# Microcontroller.net
KiCad netlist of a schematic drawn in Altium Designer
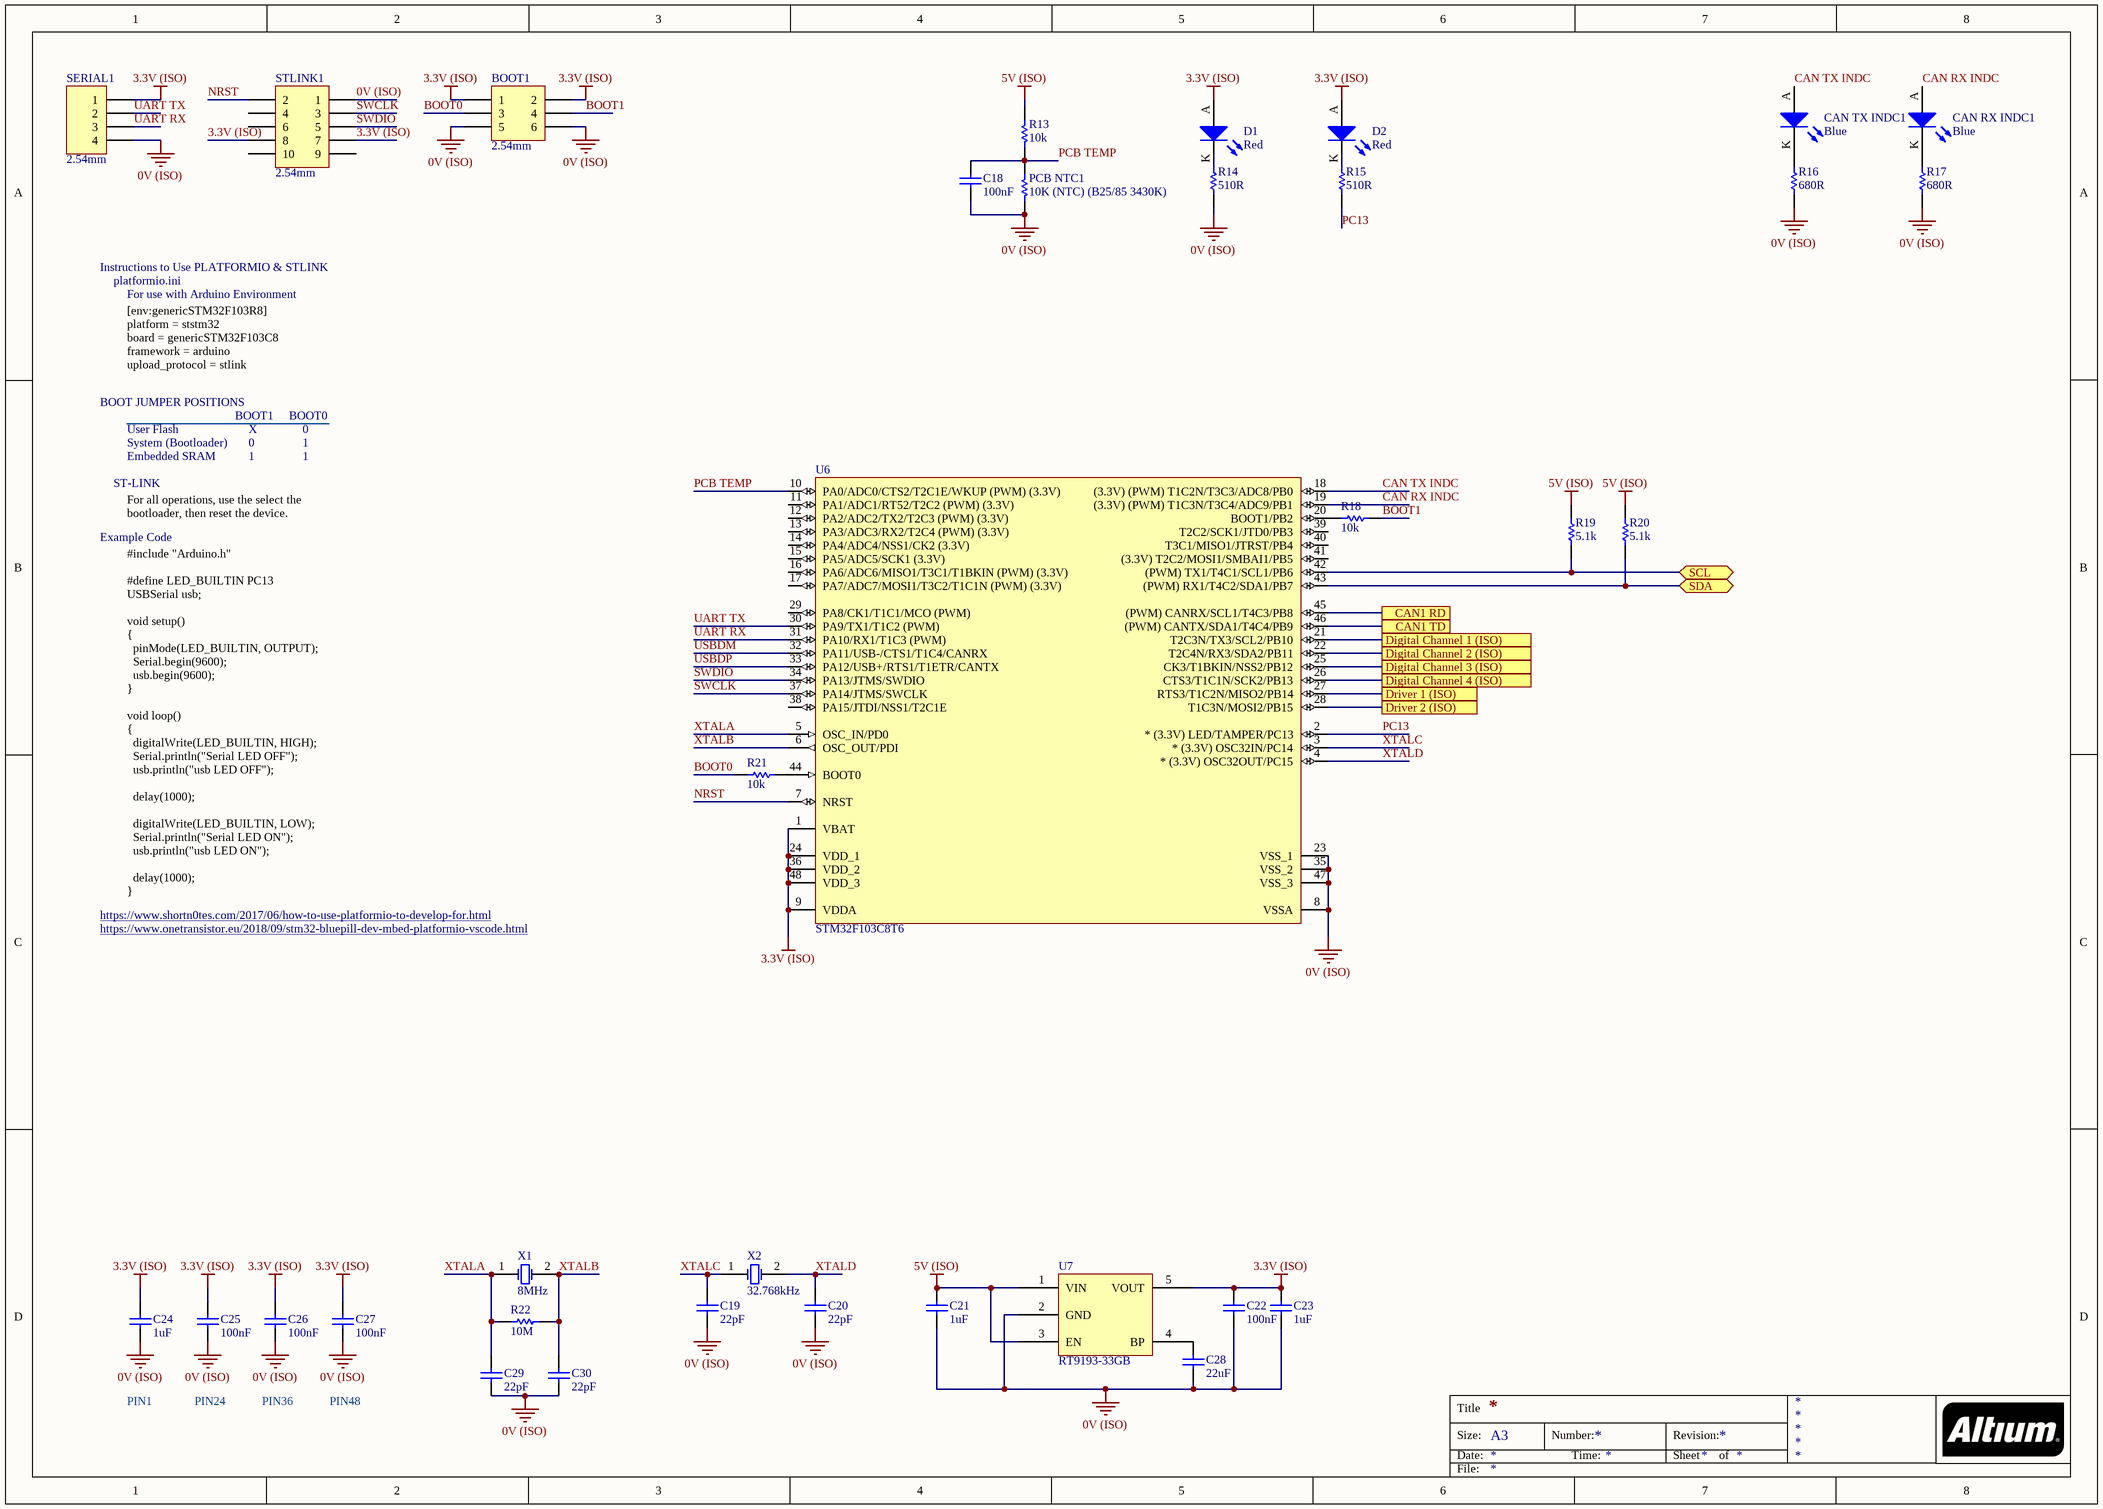
[diagram p0: Microcontroller.SchDoc]

(export (version "E")
  (design (tool "Eeschema 10.0.6"))
  (components
    (comp (ref "BOOT1")
      (value "2.54mm")
      (footprint "TH 2.54mm Header 2x3")
      (fields (field (name "PART NUMBER") "TH 2.54mm Header 2x3") (field (name "CONTACT") "NA"))
      (libsource (lib "ts_20-standard-connectors") (part "Header 2x3"))
    )
    (comp (ref "C18")
      (value "100nF")
      (footprint "0805")
      (fields
        (field (name "PART NUMBER") "GCM21BR71E104KA37L")
        (field (name "TOLERANCE") "10%")
        (field (name "MANUFACTURER") "muRata")
      )
      (libsource (lib "ts_20-standard-library") (part "Capacitor"))
    )
    (comp (ref "C19")
      (value "22pF")
      (footprint "0805")
      (fields
        (field (name "PART NUMBER") "GCM21B5C1H220JA37L")
        (field (name "TOLERANCE") "5%")
        (field (name "MANUFACTURER") "muRata")
      )
      (libsource (lib "ts_20-standard-library") (part "Capacitor"))
    )
    (comp (ref "C20")
      (value "22pF")
      (footprint "0805")
      (fields
        (field (name "PART NUMBER") "GCM21B5C1H220JA37L")
        (field (name "TOLERANCE") "5%")
        (field (name "MANUFACTURER") "muRata")
      )
      (libsource (lib "ts_20-standard-library") (part "Capacitor"))
    )
    (comp (ref "C21")
      (value "1uF")
      (footprint "0805")
      (fields
        (field (name "PART NUMBER") "AC0805KKX7R8BB105")
        (field (name "TOLERANCE") "10%")
        (field (name "MANUFACTURER") "YAGEO")
      )
      (libsource (lib "ts_20-standard-library") (part "Capacitor"))
    )
    (comp (ref "C22")
      (value "100nF")
      (footprint "0805")
      (fields
        (field (name "PART NUMBER") "GCM21BR71E104KA37L")
        (field (name "TOLERANCE") "10%")
        (field (name "MANUFACTURER") "muRata")
      )
      (libsource (lib "ts_20-standard-library") (part "Capacitor"))
    )
    (comp (ref "C23")
      (value "1uF")
      (footprint "0805")
      (fields
        (field (name "PART NUMBER") "AC0805KKX7R8BB105")
        (field (name "TOLERANCE") "10%")
        (field (name "MANUFACTURER") "YAGEO")
      )
      (libsource (lib "ts_20-standard-library") (part "Capacitor"))
    )
    (comp (ref "C24")
      (value "1uF")
      (footprint "0805")
      (fields
        (field (name "PART NUMBER") "AC0805KKX7R8BB105")
        (field (name "TOLERANCE") "10%")
        (field (name "MANUFACTURER") "YAGEO")
      )
      (libsource (lib "ts_20-standard-library") (part "Capacitor"))
    )
    (comp (ref "C25")
      (value "100nF")
      (footprint "0805")
      (fields
        (field (name "PART NUMBER") "GCM21BR71E104KA37L")
        (field (name "TOLERANCE") "10%")
        (field (name "MANUFACTURER") "muRata")
      )
      (libsource (lib "ts_20-standard-library") (part "Capacitor"))
    )
    (comp (ref "C26")
      (value "100nF")
      (footprint "0805")
      (fields
        (field (name "PART NUMBER") "GCM21BR71E104KA37L")
        (field (name "TOLERANCE") "10%")
        (field (name "MANUFACTURER") "muRata")
      )
      (libsource (lib "ts_20-standard-library") (part "Capacitor"))
    )
    (comp (ref "C27")
      (value "100nF")
      (footprint "0805")
      (fields
        (field (name "PART NUMBER") "GCM21BR71E104KA37L")
        (field (name "TOLERANCE") "10%")
        (field (name "MANUFACTURER") "muRata")
      )
      (libsource (lib "ts_20-standard-library") (part "Capacitor"))
    )
    (comp (ref "C28")
      (value "22uF")
      (footprint "0805")
      (fields
        (field (name "PART NUMBER") "GRM21BR61A226ME51L")
        (field (name "TOLERANCE") "20%")
        (field (name "MANUFACTURER") "muRata")
      )
      (libsource (lib "ts_20-standard-library") (part "Capacitor"))
    )
    (comp (ref "C29")
      (value "22pF")
      (footprint "0805")
      (fields
        (field (name "PART NUMBER") "GCM21B5C1H220JA37L")
        (field (name "TOLERANCE") "5%")
        (field (name "MANUFACTURER") "muRata")
      )
      (libsource (lib "ts_20-standard-library") (part "Capacitor"))
    )
    (comp (ref "C30")
      (value "22pF")
      (footprint "0805")
      (fields
        (field (name "PART NUMBER") "GCM21B5C1H220JA37L")
        (field (name "TOLERANCE") "5%")
        (field (name "MANUFACTURER") "muRata")
      )
      (libsource (lib "ts_20-standard-library") (part "Capacitor"))
    )
    (comp (ref "CAN RX INDC1")
      (value "Blue")
      (footprint "0805 LED")
      (description "LED BLUE CLEAR 2012 SMD")
      (fields
        (field (name "PART NUMBER") "SML-MN2BCTT86C")
        (field (name "MANUFACTURER") "ROHM Semiconductor")
      )
      (libsource (lib "ts_20-standard-library") (part "LED"))
    )
    (comp (ref "CAN TX INDC1")
      (value "Blue")
      (footprint "0805 LED")
      (description "LED BLUE CLEAR 2012 SMD")
      (fields
        (field (name "PART NUMBER") "SML-MN2BCTT86C")
        (field (name "MANUFACTURER") "ROHM Semiconductor")
      )
      (libsource (lib "ts_20-standard-library") (part "LED"))
    )
    (comp (ref "D1")
      (value "Red")
      (footprint "0805 LED")
      (description "Red LED Indication - Discrete 1.75V 0805 (2012 Metric)")
      (fields (field (name "MANUFACTURER") "ROHM Semiconductor") (field (name "PART NUMBER") "SML-210LTT86"))
      (libsource (lib "ts_20-standard-library") (part "LED"))
    )
    (comp (ref "D2")
      (value "Red")
      (footprint "0805 LED")
      (description "Red LED Indication - Discrete 1.75V 0805 (2012 Metric)")
      (fields (field (name "MANUFACTURER") "ROHM Semiconductor") (field (name "PART NUMBER") "SML-210LTT86"))
      (libsource (lib "ts_20-standard-library") (part "LED"))
    )
    (comp (ref "PCB NTC1")
      (value "10K (NTC) (B25/85 3430K)")
      (footprint "0805")
      (fields
        (field (name "PART NUMBER") "NTCS0805E3103FLT")
        (field (name "MANUFACTURER") "Vishay Beyschlag")
        (field (name "TOLERANCE") "0.01")
      )
      (libsource (lib "ts_20-standard-library") (part "Resistor"))
    )
    (comp (ref "R13")
      (value "10k")
      (footprint "0805")
      (fields
        (field (name "PART NUMBER") "RC0805FR0710KL")
        (field (name "MANUFACTURER") "YAGEO")
        (field (name "TOLERANCE") "0.01")
      )
      (libsource (lib "ts_20-standard-library") (part "Resistor"))
    )
    (comp (ref "R14")
      (value "510R")
      (footprint "0805")
      (fields
        (field (name "MANUFACTURER") "YAGEO")
        (field (name "PART NUMBER") "RC0805FR07510RL")
        (field (name "TOLERANCE") "0.01")
      )
      (libsource (lib "ts_20-standard-library") (part "Resistor"))
    )
    (comp (ref "R15")
      (value "510R")
      (footprint "0805")
      (fields
        (field (name "MANUFACTURER") "YAGEO")
        (field (name "PART NUMBER") "RC0805FR07510RL")
        (field (name "TOLERANCE") "0.01")
      )
      (libsource (lib "ts_20-standard-library") (part "Resistor"))
    )
    (comp (ref "R16")
      (value "680R")
      (footprint "0805")
      (fields
        (field (name "PART NUMBER") "RC0805FR07680RL")
        (field (name "MANUFACTURER") "YAGEO")
        (field (name "TOLERANCE") "0.01")
      )
      (libsource (lib "ts_20-standard-library") (part "Resistor"))
    )
    (comp (ref "R17")
      (value "680R")
      (footprint "0805")
      (fields
        (field (name "PART NUMBER") "RC0805FR07680RL")
        (field (name "MANUFACTURER") "YAGEO")
        (field (name "TOLERANCE") "0.01")
      )
      (libsource (lib "ts_20-standard-library") (part "Resistor"))
    )
    (comp (ref "R18")
      (value "10k")
      (footprint "0805")
      (fields
        (field (name "PART NUMBER") "RC0805FR0710KL")
        (field (name "MANUFACTURER") "YAGEO")
        (field (name "TOLERANCE") "0.01")
      )
      (libsource (lib "ts_20-standard-library") (part "Resistor"))
    )
    (comp (ref "R19")
      (value "5.1k")
      (footprint "0805")
      (fields
        (field (name "PART NUMBER") "RC0805FR075K1L")
        (field (name "MANUFACTURER") "YAGEO")
        (field (name "TOLERANCE") "0.01")
      )
      (libsource (lib "ts_20-standard-library") (part "Resistor"))
    )
    (comp (ref "R20")
      (value "5.1k")
      (footprint "0805")
      (fields
        (field (name "PART NUMBER") "RC0805FR075K1L")
        (field (name "MANUFACTURER") "YAGEO")
        (field (name "TOLERANCE") "0.01")
      )
      (libsource (lib "ts_20-standard-library") (part "Resistor"))
    )
    (comp (ref "R21")
      (value "10k")
      (footprint "0805")
      (fields
        (field (name "PART NUMBER") "RC0805FR0710KL")
        (field (name "MANUFACTURER") "YAGEO")
        (field (name "TOLERANCE") "0.01")
      )
      (libsource (lib "ts_20-standard-library") (part "Resistor"))
    )
    (comp (ref "R22")
      (value "10M")
      (footprint "0805")
      (fields
        (field (name "PART NUMBER") "RC0805FR0710ML")
        (field (name "MANUFACTURER") "YAGEO")
        (field (name "TOLERANCE") "0.01")
      )
      (libsource (lib "ts_20-standard-library") (part "Resistor"))
    )
    (comp (ref "SERIAL1")
      (value "2.54mm")
      (footprint "TH 2.54mm Header 1x4")
      (fields (field (name "PART NUMBER") "TH 2.54mm Header 1x4") (field (name "CONTACT") "NA"))
      (libsource (lib "ts_20-standard-connectors") (part "Header 1x4"))
    )
    (comp (ref "STLINK1")
      (value "2.54mm")
      (footprint "TH 2.54mm Header 2x5")
      (fields (field (name "PART NUMBER") "TH 2.54mm Header 2x5") (field (name "CONTACT") "NA"))
      (libsource (lib "ts_20-standard-connectors") (part "Header 2x5"))
    )
    (comp (ref "U6")
      (value "STM32F103C8T6")
      (footprint "STM 48-LQFP")
      (description "ARM® Cortex®-M3 STM32F1 Microcontroller IC 32-Bit 72MHz 64KB (64K x 8) FLASH")
      (fields
        (field (name "MANUFACTURER") "STMicroelectronics")
        (field (name "DIGIKEY PART NUMBER") "497-6063-ND")
      )
      (libsource (lib "ts_20-standard-library") (part "STM32F103C8T6"))
    )
    (comp (ref "U7")
      (value "RT9193-33GB")
      (footprint "RICHTEK SOT-23-5")
      (description "IC REG LINEAR 3.3V 300MA SOT23-5")
      (fields (field (name "MANUFACTURER") "Richtek") (field (name "DIGIKEY PART NUMBER") "1028-1014-1-ND"))
      (libsource (lib "ts_20-standard-library") (part "RT9193-33GB"))
    )
    (comp (ref "X1")
      (value "8MHz")
      (footprint "Abracon HC-49/US")
      (fields
        (field (name "PART NUMBER") "ABLS-8.000MHZ-B4-T")
        (field (name "MANUFACTURER") "Abracon LLC")
        (field (name "DIGIKEY PART NUMBER") "535-10212-2-ND")
      )
      (libsource (lib "ts_20-standard-library") (part "Crystal"))
    )
    (comp (ref "X2")
      (value "32.768kHz")
      (footprint "EPSON 2-SMD")
      (fields
        (field (name "PART NUMBER") "FC-135 32.7680KA-A5")
        (field (name "MANUFACTURER") "EPSON")
        (field (name "DIGIKEY PART NUMBER") "SER4103TR-ND")
      )
      (libsource (lib "ts_20-standard-library") (part "Crystal"))
    )
  )
  (nets
    (net (code "1") (name "/BOOT0") (class "Default")
      (node (ref "BOOT1") (pin "3") (pinfunction "3_3") (pintype "passive"))
      (node (ref "R21") (pin "1") (pinfunction "1_1") (pintype "passive"))
    )
    (net (code "2") (name "/BOOT1") (class "Default")
      (node (ref "BOOT1") (pin "4") (pinfunction "4_4") (pintype "passive"))
      (node (ref "R18") (pin "2") (pinfunction "2_2") (pintype "passive"))
    )
    (net (code "3") (name "/CAN RX INDC") (class "Default")
      (node (ref "CAN RX INDC1") (pin "A") (pinfunction "A_A") (pintype "passive"))
      (node (ref "U6") (pin "19") (pinfunction "(3.3V)_(PWM)_T1C3N/T3C4/ADC9/PB1_19") (pintype "bidirectional"))
    )
    (net (code "4") (name "/CAN TX INDC") (class "Default")
      (node (ref "CAN TX INDC1") (pin "A") (pinfunction "A_A") (pintype "passive"))
      (node (ref "U6") (pin "18") (pinfunction "(3.3V)_(PWM)_T1C2N/T3C3/ADC8/PB0_18") (pintype "bidirectional"))
    )
    (net (code "5") (name "/CAN1 RD") (class "Default")
      (node (ref "U6") (pin "45") (pinfunction "(PWM)_CANRX/SCL1/T4C3/PB8_45") (pintype "bidirectional"))
    )
    (net (code "6") (name "/CAN1 TD") (class "Default")
      (node (ref "U6") (pin "46") (pinfunction "(PWM)_CANTX/SDA1/T4C4/PB9_46") (pintype "bidirectional"))
    )
    (net (code "7") (name "/Digital Channel 1 (ISO)") (class "Default")
      (node (ref "U6") (pin "21") (pinfunction "T2C3N/TX3/SCL2/PB10_21") (pintype "bidirectional"))
    )
    (net (code "8") (name "/Digital Channel 2 (ISO)") (class "Default")
      (node (ref "U6") (pin "22") (pinfunction "T2C4N/RX3/SDA2/PB11_22") (pintype "bidirectional"))
    )
    (net (code "9") (name "/Digital Channel 3 (ISO)") (class "Default")
      (node (ref "U6") (pin "25") (pinfunction "CK3/T1BKIN/NSS2/PB12_25") (pintype "bidirectional"))
    )
    (net (code "10") (name "/Digital Channel 4 (ISO)") (class "Default")
      (node (ref "U6") (pin "26") (pinfunction "CTS3/T1C1N/SCK2/PB13_26") (pintype "bidirectional"))
    )
    (net (code "11") (name "/Driver 1 (ISO)") (class "Default")
      (node (ref "U6") (pin "27") (pinfunction "RTS3/T1C2N/MISO2/PB14_27") (pintype "bidirectional"))
    )
    (net (code "12") (name "/Driver 2 (ISO)") (class "Default")
      (node (ref "U6") (pin "28") (pinfunction "T1C3N/MOSI2/PB15_28") (pintype "bidirectional"))
    )
    (net (code "13") (name "/NRST") (class "Default")
      (node (ref "STLINK1") (pin "2") (pinfunction "2_2") (pintype "passive"))
      (node (ref "U6") (pin "7") (pinfunction "NRST_7") (pintype "bidirectional"))
    )
    (net (code "14") (name "/PC13") (class "Default")
      (node (ref "R15") (pin "1") (pinfunction "1_1") (pintype "passive"))
      (node (ref "U6") (pin "2") (pinfunction "*_(3.3V)_LED/TAMPER/PC13_2") (pintype "bidirectional"))
    )
    (net (code "15") (name "/PCB TEMP") (class "Default")
      (node (ref "C18") (pin "2") (pinfunction "2_2") (pintype "passive"))
      (node (ref "PCB NTC1") (pin "2") (pinfunction "2_2") (pintype "passive"))
      (node (ref "R13") (pin "1") (pinfunction "1_1") (pintype "passive"))
      (node (ref "U6") (pin "10") (pinfunction "PA0/ADC0/CTS2/T2C1E/WKUP_(PWM)_(3.3V)_10") (pintype "bidirectional"))
    )
    (net (code "16") (name "/SCL") (class "Default")
      (node (ref "R19") (pin "1") (pinfunction "1_1") (pintype "passive"))
      (node (ref "U6") (pin "42") (pinfunction "(PWM)_TX1/T4C1/SCL1/PB6_42") (pintype "bidirectional"))
    )
    (net (code "17") (name "/SDA") (class "Default")
      (node (ref "R20") (pin "1") (pinfunction "1_1") (pintype "passive"))
      (node (ref "U6") (pin "43") (pinfunction "(PWM)_RX1/T4C2/SDA1/PB7_43") (pintype "bidirectional"))
    )
    (net (code "18") (name "/SWCLK") (class "Default")
      (node (ref "STLINK1") (pin "3") (pinfunction "3_3") (pintype "passive"))
      (node (ref "U6") (pin "37") (pinfunction "PA14/JTMS/SWCLK_37") (pintype "bidirectional"))
    )
    (net (code "19") (name "/SWDIO") (class "Default")
      (node (ref "STLINK1") (pin "5") (pinfunction "5_5") (pintype "passive"))
      (node (ref "U6") (pin "34") (pinfunction "PA13/JTMS/SWDIO_34") (pintype "bidirectional"))
    )
    (net (code "20") (name "/UART RX") (class "Default")
      (node (ref "SERIAL1") (pin "3") (pinfunction "3_3") (pintype "passive"))
      (node (ref "U6") (pin "31") (pinfunction "PA10/RX1/T1C3_(PWM)_31") (pintype "bidirectional"))
    )
    (net (code "21") (name "/UART TX") (class "Default")
      (node (ref "SERIAL1") (pin "2") (pinfunction "2_2") (pintype "passive"))
      (node (ref "U6") (pin "30") (pinfunction "PA9/TX1/T1C2_(PWM)_30") (pintype "bidirectional"))
    )
    (net (code "22") (name "/USBDM") (class "Default")
      (node (ref "U6") (pin "32") (pinfunction "PA11/USB-/CTS1/T1C4/CANRX_32") (pintype "bidirectional"))
    )
    (net (code "23") (name "/USBDP") (class "Default")
      (node (ref "U6") (pin "33") (pinfunction "PA12/USB+/RTS1/T1ETR/CANTX_33") (pintype "bidirectional"))
    )
    (net (code "24") (name "/XTALA") (class "Default")
      (node (ref "C29") (pin "2") (pinfunction "2_2") (pintype "passive"))
      (node (ref "R22") (pin "2") (pinfunction "2_2") (pintype "passive"))
      (node (ref "U6") (pin "5") (pinfunction "OSC_IN/PD0_5") (pintype "input"))
      (node (ref "X1") (pin "1") (pinfunction "OSC1_1") (pintype "passive"))
    )
    (net (code "25") (name "/XTALB") (class "Default")
      (node (ref "C30") (pin "2") (pinfunction "2_2") (pintype "passive"))
      (node (ref "R22") (pin "1") (pinfunction "1_1") (pintype "passive"))
      (node (ref "U6") (pin "6") (pinfunction "OSC_OUT/PDI_6") (pintype "output"))
      (node (ref "X1") (pin "2") (pinfunction "OSC2_2") (pintype "passive"))
    )
    (net (code "26") (name "/XTALC") (class "Default")
      (node (ref "C19") (pin "2") (pinfunction "2_2") (pintype "passive"))
      (node (ref "U6") (pin "3") (pinfunction "*_(3.3V)_OSC32IN/PC14_3") (pintype "bidirectional"))
      (node (ref "X2") (pin "1") (pinfunction "OSC1_1") (pintype "passive"))
    )
    (net (code "27") (name "/XTALD") (class "Default")
      (node (ref "C20") (pin "2") (pinfunction "2_2") (pintype "passive"))
      (node (ref "U6") (pin "4") (pinfunction "*_(3.3V)_OSC32OUT/PC15_4") (pintype "bidirectional"))
      (node (ref "X2") (pin "2") (pinfunction "OSC2_2") (pintype "passive"))
    )
    (net (code "28") (name "0V (ISO)") (class "Default")
      (node (ref "BOOT1") (pin "5") (pinfunction "5_5") (pintype "passive"))
      (node (ref "BOOT1") (pin "6") (pinfunction "6_6") (pintype "passive"))
      (node (ref "C18") (pin "1") (pinfunction "1_1") (pintype "passive"))
      (node (ref "C19") (pin "1") (pinfunction "1_1") (pintype "passive"))
      (node (ref "C20") (pin "1") (pinfunction "1_1") (pintype "passive"))
      (node (ref "C21") (pin "1") (pinfunction "1_1") (pintype "passive"))
      (node (ref "C22") (pin "1") (pinfunction "1_1") (pintype "passive"))
      (node (ref "C23") (pin "1") (pinfunction "1_1") (pintype "passive"))
      (node (ref "C24") (pin "1") (pinfunction "1_1") (pintype "passive"))
      (node (ref "C25") (pin "1") (pinfunction "1_1") (pintype "passive"))
      (node (ref "C26") (pin "1") (pinfunction "1_1") (pintype "passive"))
      (node (ref "C27") (pin "1") (pinfunction "1_1") (pintype "passive"))
      (node (ref "C28") (pin "1") (pinfunction "1_1") (pintype "passive"))
      (node (ref "C29") (pin "1") (pinfunction "1_1") (pintype "passive"))
      (node (ref "C30") (pin "1") (pinfunction "1_1") (pintype "passive"))
      (node (ref "PCB NTC1") (pin "1") (pinfunction "1_1") (pintype "passive"))
      (node (ref "R14") (pin "1") (pinfunction "1_1") (pintype "passive"))
      (node (ref "R16") (pin "1") (pinfunction "1_1") (pintype "passive"))
      (node (ref "R17") (pin "1") (pinfunction "1_1") (pintype "passive"))
      (node (ref "SERIAL1") (pin "4") (pinfunction "4_4") (pintype "passive"))
      (node (ref "STLINK1") (pin "1") (pinfunction "1_1") (pintype "passive"))
      (node (ref "U6") (pin "23") (pinfunction "VSS_1_23") (pintype "power_in"))
      (node (ref "U6") (pin "35") (pinfunction "VSS_2_35") (pintype "power_in"))
      (node (ref "U6") (pin "47") (pinfunction "VSS_3_47") (pintype "power_in"))
      (node (ref "U6") (pin "8") (pinfunction "VSSA_8") (pintype "power_in"))
      (node (ref "U7") (pin "2") (pinfunction "GND_2") (pintype "passive"))
    )
    (net (code "29") (name "3.3V (ISO)") (class "Default")
      (node (ref "BOOT1") (pin "1") (pinfunction "1_1") (pintype "passive"))
      (node (ref "BOOT1") (pin "2") (pinfunction "2_2") (pintype "passive"))
      (node (ref "C22") (pin "2") (pinfunction "2_2") (pintype "passive"))
      (node (ref "C23") (pin "2") (pinfunction "2_2") (pintype "passive"))
      (node (ref "C24") (pin "2") (pinfunction "2_2") (pintype "passive"))
      (node (ref "C25") (pin "2") (pinfunction "2_2") (pintype "passive"))
      (node (ref "C26") (pin "2") (pinfunction "2_2") (pintype "passive"))
      (node (ref "C27") (pin "2") (pinfunction "2_2") (pintype "passive"))
      (node (ref "D1") (pin "A") (pinfunction "A_A") (pintype "passive"))
      (node (ref "D2") (pin "A") (pinfunction "A_A") (pintype "passive"))
      (node (ref "SERIAL1") (pin "1") (pinfunction "1_1") (pintype "passive"))
      (node (ref "STLINK1") (pin "7") (pinfunction "7_7") (pintype "passive"))
      (node (ref "STLINK1") (pin "8") (pinfunction "8_8") (pintype "passive"))
      (node (ref "U6") (pin "1") (pinfunction "VBAT_1") (pintype "power_in"))
      (node (ref "U6") (pin "24") (pinfunction "VDD_1_24") (pintype "power_in"))
      (node (ref "U6") (pin "36") (pinfunction "VDD_2_36") (pintype "power_in"))
      (node (ref "U6") (pin "48") (pinfunction "VDD_3_48") (pintype "power_in"))
      (node (ref "U6") (pin "9") (pinfunction "VDDA_9") (pintype "power_in"))
      (node (ref "U7") (pin "5") (pinfunction "VOUT_5") (pintype "passive"))
    )
    (net (code "30") (name "5V (ISO)") (class "Default")
      (node (ref "C21") (pin "2") (pinfunction "2_2") (pintype "passive"))
      (node (ref "R13") (pin "2") (pinfunction "2_2") (pintype "passive"))
      (node (ref "R19") (pin "2") (pinfunction "2_2") (pintype "passive"))
      (node (ref "R20") (pin "2") (pinfunction "2_2") (pintype "passive"))
      (node (ref "U7") (pin "1") (pinfunction "VIN_1") (pintype "passive"))
      (node (ref "U7") (pin "3") (pinfunction "EN_3") (pintype "passive"))
    )
    (net (code "31") (name "Net-(CAN RX INDC1-PadK)") (class "Default")
      (node (ref "CAN RX INDC1") (pin "K") (pinfunction "K_K") (pintype "passive"))
      (node (ref "R17") (pin "2") (pinfunction "2_2") (pintype "passive"))
    )
    (net (code "32") (name "Net-(CAN TX INDC1-PadK)") (class "Default")
      (node (ref "CAN TX INDC1") (pin "K") (pinfunction "K_K") (pintype "passive"))
      (node (ref "R16") (pin "2") (pinfunction "2_2") (pintype "passive"))
    )
    (net (code "33") (name "Net-(D1-PadK)") (class "Default")
      (node (ref "D1") (pin "K") (pinfunction "K_K") (pintype "passive"))
      (node (ref "R14") (pin "2") (pinfunction "2_2") (pintype "passive"))
    )
    (net (code "34") (name "Net-(D2-PadK)") (class "Default")
      (node (ref "D2") (pin "K") (pinfunction "K_K") (pintype "passive"))
      (node (ref "R15") (pin "2") (pinfunction "2_2") (pintype "passive"))
    )
    (net (code "35") (name "Net-(U6-BOOT0)") (class "Default")
      (node (ref "R21") (pin "2") (pinfunction "2_2") (pintype "passive"))
      (node (ref "U6") (pin "44") (pinfunction "BOOT0_44") (pintype "input"))
    )
    (net (code "36") (name "Net-(U6-BOOT1{slash}PB2)") (class "Default")
      (node (ref "R18") (pin "1") (pinfunction "1_1") (pintype "passive"))
      (node (ref "U6") (pin "20") (pinfunction "BOOT1/PB2_20") (pintype "bidirectional"))
    )
    (net (code "37") (name "Net-(U7-BP)") (class "Default")
      (node (ref "C28") (pin "2") (pinfunction "2_2") (pintype "passive"))
      (node (ref "U7") (pin "4") (pinfunction "BP_4") (pintype "passive"))
    )
    (net (code "38") (name "unconnected-(STLINK1-Pad4)") (class "Default")
      (node (ref "STLINK1") (pin "4") (pinfunction "4_4") (pintype "passive"))
    )
    (net (code "39") (name "unconnected-(STLINK1-Pad6)") (class "Default")
      (node (ref "STLINK1") (pin "6") (pinfunction "6_6") (pintype "passive"))
    )
    (net (code "40") (name "unconnected-(STLINK1-Pad9)") (class "Default")
      (node (ref "STLINK1") (pin "9") (pinfunction "9_9") (pintype "passive"))
    )
    (net (code "41") (name "unconnected-(STLINK1-Pad10)") (class "Default")
      (node (ref "STLINK1") (pin "10") (pinfunction "10_10") (pintype "passive"))
    )
    (net (code "42") (name "unconnected-(U6-(3.3V)_T2C2{slash}MOSI1{slash}SMBAI1{slash}PB5-Pad41)") (class "Default")
      (node (ref "U6") (pin "41") (pinfunction "(3.3V)_T2C2/MOSI1/SMBAI1/PB5_41") (pintype "bidirectional"))
    )
    (net (code "43") (name "unconnected-(U6-PA1{slash}ADC1{slash}RT52{slash}T2C2_(PWM)_(3.3V)-Pad11)") (class "Default")
      (node (ref "U6") (pin "11") (pinfunction "PA1/ADC1/RT52/T2C2_(PWM)_(3.3V)_11") (pintype "bidirectional"))
    )
    (net (code "44") (name "unconnected-(U6-PA2{slash}ADC2{slash}TX2{slash}T2C3_(PWM)_(3.3V)-Pad12)") (class "Default")
      (node (ref "U6") (pin "12") (pinfunction "PA2/ADC2/TX2/T2C3_(PWM)_(3.3V)_12") (pintype "bidirectional"))
    )
    (net (code "45") (name "unconnected-(U6-PA3{slash}ADC3{slash}RX2{slash}T2C4_(PWM)_(3.3V)-Pad13)") (class "Default")
      (node (ref "U6") (pin "13") (pinfunction "PA3/ADC3/RX2/T2C4_(PWM)_(3.3V)_13") (pintype "bidirectional"))
    )
    (net (code "46") (name "unconnected-(U6-PA4{slash}ADC4{slash}NSS1{slash}CK2_(3.3V)-Pad14)") (class "Default")
      (node (ref "U6") (pin "14") (pinfunction "PA4/ADC4/NSS1/CK2_(3.3V)_14") (pintype "bidirectional"))
    )
    (net (code "47") (name "unconnected-(U6-PA5{slash}ADC5{slash}SCK1_(3.3V)-Pad15)") (class "Default")
      (node (ref "U6") (pin "15") (pinfunction "PA5/ADC5/SCK1_(3.3V)_15") (pintype "bidirectional"))
    )
    (net (code "48") (name "unconnected-(U6-PA6{slash}ADC6{slash}MISO1{slash}T3C1{slash}T1BKIN_(PWM)_(3.3V)-Pad16)") (class "Default")
      (node (ref "U6") (pin "16") (pinfunction "PA6/ADC6/MISO1/T3C1/T1BKIN_(PWM)_(3.3V)_16") (pintype "bidirectional"))
    )
    (net (code "49") (name "unconnected-(U6-PA7{slash}ADC7{slash}MOSI1{slash}T3C2{slash}T1C1N_(PWM)_(3.3V)-Pad17)") (class "Default")
      (node (ref "U6") (pin "17") (pinfunction "PA7/ADC7/MOSI1/T3C2/T1C1N_(PWM)_(3.3V)_17") (pintype "bidirectional"))
    )
    (net (code "50") (name "unconnected-(U6-PA8{slash}CK1{slash}T1C1{slash}MCO_(PWM)-Pad29)") (class "Default")
      (node (ref "U6") (pin "29") (pinfunction "PA8/CK1/T1C1/MCO_(PWM)_29") (pintype "bidirectional"))
    )
    (net (code "51") (name "unconnected-(U6-PA15{slash}JTDI{slash}NSS1{slash}T2C1E-Pad38)") (class "Default")
      (node (ref "U6") (pin "38") (pinfunction "PA15/JTDI/NSS1/T2C1E_38") (pintype "bidirectional"))
    )
    (net (code "52") (name "unconnected-(U6-T2C2{slash}SCK1{slash}JTD0{slash}PB3-Pad39)") (class "Default")
      (node (ref "U6") (pin "39") (pinfunction "T2C2/SCK1/JTD0/PB3_39") (pintype "bidirectional"))
    )
    (net (code "53") (name "unconnected-(U6-T3C1{slash}MISO1{slash}JTRST{slash}PB4-Pad40)") (class "Default")
      (node (ref "U6") (pin "40") (pinfunction "T3C1/MISO1/JTRST/PB4_40") (pintype "bidirectional"))
    )
  )
)
